# EVK-NORA-W1_SCHEM_0002_Power.net
KiCad netlist of a schematic drawn in Altium Designer
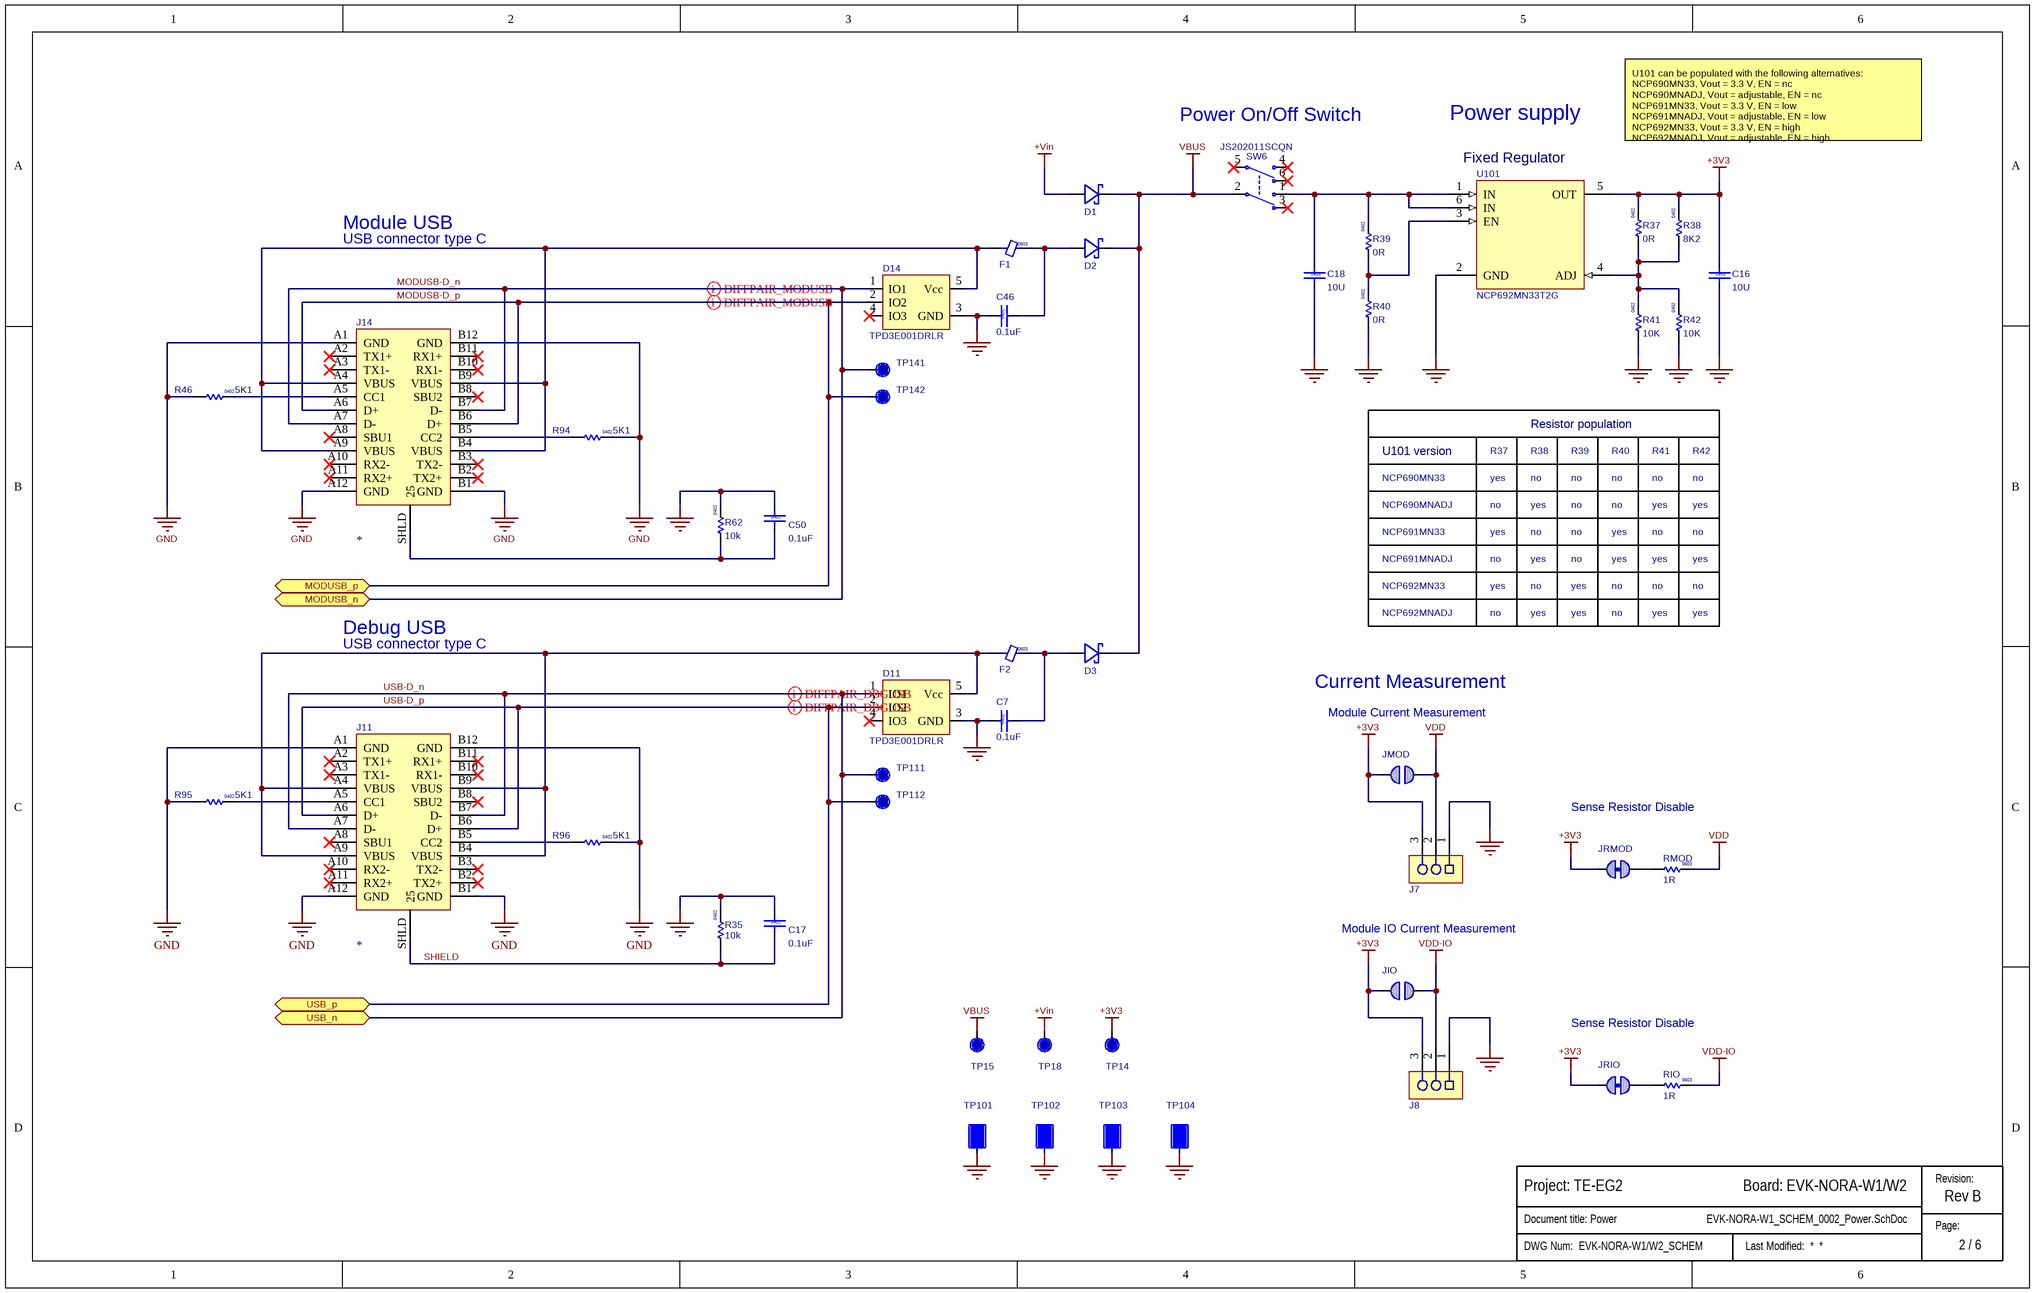
[diagram p0: EVK-NORA-W1_SCHEM_0002_Power.SchDoc]

(export (version "E")
  (design (tool "Eeschema 10.0.6"))
  (components
    (comp (ref "C7")
      (value "0.1uF")
      (footprint "Cap 0402 HD")
      (description "Cap, Ceramic 0.1uF 10V 10% X5R 0402")
      (fields
        (field (name "SIZE") "0402")
        (field (name "PART NUMBER") "120-00016")
        (field (name "MANUFACTURER") "Murata Electronics North America")
      )
      (libsource (lib "Arena_Parts_DB_Lib") (part "Cap Chip"))
    )
    (comp (ref "C16")
      (value "10U")
      (footprint "Cap 0603 HD")
      (description "CAP CER X7R 0603 10U 20% 10V")
      (fields
        (field (name "SIZE") "0603")
        (field (name "PART NUMBER") "UBXH01-0000310")
        (field (name "TOLERANCE") "20%")
        (field (name "EDITOR") "michael.hein")
        (field (name "RELEASED BY") "martin.grasse")
      )
      (libsource (lib "UBX_Parts_DB_Lib") (part "Cap Chip"))
    )
    (comp (ref "C17")
      (value "0.1uF")
      (footprint "Cap 0402 HD")
      (description "Cap, Ceramic 0.1uF 10V 10% X5R 0402")
      (fields
        (field (name "SIZE") "0402")
        (field (name "PART NUMBER") "120-00016")
        (field (name "MANUFACTURER") "Murata Electronics North America")
      )
      (libsource (lib "Arena_Parts_DB_Lib") (part "Cap Chip"))
    )
    (comp (ref "C18")
      (value "10U")
      (footprint "Cap 0603 HD")
      (description "CAP CER X7R 0603 10U 20% 10V")
      (fields
        (field (name "SIZE") "0603")
        (field (name "PART NUMBER") "UBXH01-0000310")
        (field (name "TOLERANCE") "20%")
        (field (name "EDITOR") "michael.hein")
        (field (name "RELEASED BY") "martin.grasse")
      )
      (libsource (lib "UBX_Parts_DB_Lib") (part "Cap Chip"))
    )
    (comp (ref "C46")
      (value "0.1uF")
      (footprint "Cap 0402 HD")
      (description "Cap, Ceramic 0.1uF 10V 10% X5R 0402")
      (fields
        (field (name "SIZE") "0402")
        (field (name "PART NUMBER") "120-00016")
        (field (name "MANUFACTURER") "Murata Electronics North America")
      )
      (libsource (lib "Arena_Parts_DB_Lib") (part "Cap Chip"))
    )
    (comp (ref "C50")
      (value "0.1uF")
      (footprint "Cap 0402 HD")
      (description "Cap, Ceramic 0.1uF 10V 10% X5R 0402")
      (fields
        (field (name "SIZE") "0402")
        (field (name "PART NUMBER") "120-00016")
        (field (name "MANUFACTURER") "Murata Electronics North America")
      )
      (libsource (lib "Arena_Parts_DB_Lib") (part "Cap Chip"))
    )
    (comp (ref "D1")
      (value "110-00005")
      (footprint "SOD-123F_U")
      (description "Diode, Schottky, 20V 1A SOD-123F, 340mV Vf @ 1A\nMBR120VLSFT3G")
      (fields (field (name "VOLTAGE") "20V"))
      (libsource (lib "Arena_Parts_DB_Lib") (part "Diode_Schottky"))
    )
    (comp (ref "D2")
      (value "110-00005")
      (footprint "SOD-123F_U")
      (description "Diode, Schottky, 20V 1A SOD-123F, 340mV Vf @ 1A\nMBR120VLSFT3G")
      (fields (field (name "VOLTAGE") "20V"))
      (libsource (lib "Arena_Parts_DB_Lib") (part "Diode_Schottky"))
    )
    (comp (ref "D3")
      (value "110-00005")
      (footprint "SOD-123F_U")
      (description "Diode, Schottky, 20V 1A SOD-123F, 340mV Vf @ 1A\nMBR120VLSFT3G")
      (fields (field (name "VOLTAGE") "20V"))
      (libsource (lib "Arena_Parts_DB_Lib") (part "Diode_Schottky"))
    )
    (comp (ref "D11")
      (value "110-00018")
      (footprint "SOT-553")
      (description "LOW-CAPACITANCE 3-CHANNEL ESD-PROTECTION ARRAY")
      (fields
        (field (name "MANUFACTURER P/N") "TPD3E001DRLR")
        (field (name "MANUFACTURER") "Texas Instruments")
        (field (name "VOLTAGE") "5V")
      )
      (libsource (lib "Arena_Parts_DB_Lib") (part "TPD3E001"))
    )
    (comp (ref "D14")
      (value "110-00018")
      (footprint "SOT-553")
      (description "LOW-CAPACITANCE 3-CHANNEL ESD-PROTECTION ARRAY")
      (fields
        (field (name "MANUFACTURER P/N") "TPD3E001DRLR")
        (field (name "MANUFACTURER") "Texas Instruments")
        (field (name "VOLTAGE") "5V")
      )
      (libsource (lib "Arena_Parts_DB_Lib") (part "TPD3E001"))
    )
    (comp (ref "F1")
      (value "UBXH08-0000001")
      (footprint "IND 0603 HD")
      (description "FERRITE BEAD 0603 600 OHM AT 100MHZ 600OHM 500mA")
      (fields
        (field (name "SIZE") "0603")
        (field (name "MANUFACTURER") "TDK Corporation")
        (field (name "EDITOR") "daniel.hurni")
        (field (name "RELEASED BY") "martin.frauchiger")
      )
      (libsource (lib "UBX_Parts_DB_Lib") (part "FB sm"))
    )
    (comp (ref "F2")
      (value "UBXH08-0000001")
      (footprint "IND 0603 HD")
      (description "FERRITE BEAD 0603 600 OHM AT 100MHZ 600OHM 500mA")
      (fields
        (field (name "SIZE") "0603")
        (field (name "MANUFACTURER") "TDK Corporation")
        (field (name "EDITOR") "daniel.hurni")
        (field (name "RELEASED BY") "martin.frauchiger")
      )
      (libsource (lib "UBX_Parts_DB_Lib") (part "FB sm"))
    )
    (comp (ref "J7")
      (value "130-00105")
      (footprint "HDR-0.1P-3Pin-1Row-SMT")
      (description "Header, 0.100\" Pitch, 3 Pin, Vertical SMT")
      (fields (field (name "MANUFACTURER") "Harwin Inc"))
      (libsource (lib "Arena_Parts_DB_Lib") (part "CON-3Pin_1Row"))
    )
    (comp (ref "J8")
      (value "130-00105")
      (footprint "HDR-0.1P-3Pin-1Row-SMT")
      (description "Header, 0.100\" Pitch, 3 Pin, Vertical SMT")
      (fields (field (name "MANUFACTURER") "Harwin Inc"))
      (libsource (lib "Arena_Parts_DB_Lib") (part "CON-3Pin_1Row"))
    )
    (comp (ref "J11")
      (value "130-00150")
      (footprint "CON_USB-C-RA_W-6Tabs")
      (description "Connector, USB-C Receptacle, 24 Position, Surface Mount, Right Angle, Horizontal, 20V")
      (fields (field (name "MANUFACTURER P/N") "*") (field (name "VOLTAGE") "20V"))
      (libsource (lib "Arena_Parts_DB_Lib") (part "USB-24Pin_W-Shield"))
    )
    (comp (ref "J14")
      (value "130-00150")
      (footprint "CON_USB-C-RA_W-6Tabs")
      (description "Connector, USB-C Receptacle, 24 Position, Surface Mount, Right Angle, Horizontal, 20V")
      (fields (field (name "MANUFACTURER P/N") "*") (field (name "VOLTAGE") "20V"))
      (libsource (lib "Arena_Parts_DB_Lib") (part "USB-24Pin_W-Shield"))
    )
    (comp (ref "JIO")
      (value "Solderbridge-OpenDNP")
      (footprint "Solderbridge-Open")
      (description "Solderbridge-Open")
      (fields (field (name "ADDED BY") "Paul B"))
      (libsource (lib "LEGACY_Rigado_AltiumLib") (part "Solderbridge-Open"))
    )
    (comp (ref "JMOD")
      (value "Solderbridge-OpenDNP")
      (footprint "Solderbridge-Open")
      (description "Solderbridge-Open")
      (fields (field (name "ADDED BY") "Paul B"))
      (libsource (lib "LEGACY_Rigado_AltiumLib") (part "Solderbridge-Open"))
    )
    (comp (ref "JRIO")
      (value "Solderbridge-ShortDNP")
      (footprint "Solderbridge-Short")
      (description "Solderbridge-Short")
      (fields (field (name "ADDED BY") "Paul B"))
      (libsource (lib "LEGACY_Rigado_AltiumLib") (part "Solderbridge-Short"))
    )
    (comp (ref "JRMOD")
      (value "Solderbridge-ShortDNP")
      (footprint "Solderbridge-Short")
      (description "Solderbridge-Short")
      (fields (field (name "ADDED BY") "Paul B"))
      (libsource (lib "LEGACY_Rigado_AltiumLib") (part "Solderbridge-Short"))
    )
    (comp (ref "R35")
      (value "10k")
      (footprint "RES 0402 HD")
      (description "Resistor 10k ohm 1% 1/16W, 0402")
      (fields
        (field (name "SIZE") "0402")
        (field (name "PART NUMBER") "180-00024")
        (field (name "MANUFACTURER") "Rohm Semiconductor")
      )
      (libsource (lib "Arena_Parts_DB_Lib") (part "Res sm"))
    )
    (comp (ref "R37")
      (value "0R")
      (footprint "RES 0402 HD")
      (description "RES THICK FILM CHIP 0402 0R 0 100mW")
      (fields
        (field (name "SIZE") "0402")
        (field (name "PART NUMBER") "UBXH18-0003002")
        (field (name "TOLERANCE") "0")
        (field (name "EDITOR") "charlotte.biber")
        (field (name "RELEASED BY") "peter.mueller")
      )
      (libsource (lib "UBX_Parts_DB_Lib") (part "Res sm"))
    )
    (comp (ref "R38")
      (value "8K2")
      (footprint "RES 0402 HD")
      (description "RES THICK FILM CHIP 0402 8K2 1% 63mW")
      (fields
        (field (name "SIZE") "0402")
        (field (name "PART NUMBER") "UBXH18-0000138")
        (field (name "TOLERANCE") "1%")
        (field (name "EDITOR") "matej.budin")
        (field (name "RELEASED BY") "pasquale.scorca")
      )
      (libsource (lib "UBX_Parts_DB_Lib") (part "Res sm"))
    )
    (comp (ref "R39")
      (value "0R")
      (footprint "RES 0402 HD")
      (description "RES THICK FILM CHIP 0402 0R 0 100mW")
      (fields
        (field (name "SIZE") "0402")
        (field (name "PART NUMBER") "UBXH18-0003002")
        (field (name "TOLERANCE") "0")
        (field (name "EDITOR") "charlotte.biber")
        (field (name "RELEASED BY") "peter.mueller")
      )
      (libsource (lib "UBX_Parts_DB_Lib") (part "Res sm"))
    )
    (comp (ref "R40")
      (value "0R")
      (footprint "RES 0402 HD")
      (description "RES THICK FILM CHIP 0402 0R 0 100mW")
      (fields
        (field (name "SIZE") "0402")
        (field (name "PART NUMBER") "UBXH18-0003002")
        (field (name "TOLERANCE") "0")
        (field (name "EDITOR") "charlotte.biber")
        (field (name "RELEASED BY") "peter.mueller")
      )
      (libsource (lib "UBX_Parts_DB_Lib") (part "Res sm"))
    )
    (comp (ref "R41")
      (value "10K")
      (footprint "RES 0402 HD")
      (description "RES THICK FILM CHIP 0402 10K 1% 63mW")
      (fields
        (field (name "SIZE") "0402")
        (field (name "PART NUMBER") "UBXH18-0000065")
        (field (name "TOLERANCE") "1%")
        (field (name "EDITOR") "erian.bezhani")
        (field (name "RELEASED BY") "massimo.vlacci")
      )
      (libsource (lib "UBX_Parts_DB_Lib") (part "Res sm"))
    )
    (comp (ref "R42")
      (value "10K")
      (footprint "RES 0402 HD")
      (description "RES THICK FILM CHIP 0402 10K 1% 63mW")
      (fields
        (field (name "SIZE") "0402")
        (field (name "PART NUMBER") "UBXH18-0000065")
        (field (name "TOLERANCE") "1%")
        (field (name "EDITOR") "erian.bezhani")
        (field (name "RELEASED BY") "massimo.vlacci")
      )
      (libsource (lib "UBX_Parts_DB_Lib") (part "Res sm"))
    )
    (comp (ref "R46")
      (value "5K1")
      (footprint "RES 0402 HD")
      (description "RES THICK FILM CHIP 0402 5K1 5% 100mW")
      (fields
        (field (name "SIZE") "0402")
        (field (name "PART NUMBER") "UBXH18-0008066")
        (field (name "TOLERANCE") "5%")
        (field (name "EDITOR") "alvaro.nussbaum")
        (field (name "RELEASED BY") "roland.rust")
      )
      (libsource (lib "UBX_Parts_DB_Lib") (part "Res sm"))
    )
    (comp (ref "R62")
      (value "10k")
      (footprint "RES 0402 HD")
      (description "Resistor 10k ohm 1% 1/16W, 0402")
      (fields
        (field (name "SIZE") "0402")
        (field (name "PART NUMBER") "180-00024")
        (field (name "MANUFACTURER") "Rohm Semiconductor")
      )
      (libsource (lib "Arena_Lib") (part "Res sm"))
    )
    (comp (ref "R94")
      (value "5K1")
      (footprint "RES 0402 HD")
      (description "RES THICK FILM CHIP 0402 5K1 5% 100mW")
      (fields
        (field (name "SIZE") "0402")
        (field (name "PART NUMBER") "UBXH18-0008066")
        (field (name "TOLERANCE") "5%")
        (field (name "EDITOR") "alvaro.nussbaum")
        (field (name "RELEASED BY") "roland.rust")
      )
      (libsource (lib "UBX_Parts_DB_Lib") (part "Res sm"))
    )
    (comp (ref "R95")
      (value "5K1")
      (footprint "RES 0402 HD")
      (description "RES THICK FILM CHIP 0402 5K1 5% 100mW")
      (fields
        (field (name "SIZE") "0402")
        (field (name "PART NUMBER") "UBXH18-0008066")
        (field (name "TOLERANCE") "5%")
        (field (name "EDITOR") "alvaro.nussbaum")
        (field (name "RELEASED BY") "roland.rust")
      )
      (libsource (lib "UBX_Parts_DB_Lib") (part "Res sm"))
    )
    (comp (ref "R96")
      (value "5K1")
      (footprint "RES 0402 HD")
      (description "RES THICK FILM CHIP 0402 5K1 5% 100mW")
      (fields
        (field (name "SIZE") "0402")
        (field (name "PART NUMBER") "UBXH18-0008066")
        (field (name "TOLERANCE") "5%")
        (field (name "EDITOR") "alvaro.nussbaum")
        (field (name "RELEASED BY") "roland.rust")
      )
      (libsource (lib "UBX_Parts_DB_Lib") (part "Res sm"))
    )
    (comp (ref "RIO")
      (value "1R")
      (footprint "RES 0603 HD")
      (description "Resistor 1 ohm 1%, 1/10W, 0603")
      (fields
        (field (name "SIZE") "0603")
        (field (name "PART NUMBER") "180-00109")
        (field (name "MANUFACTURER") "Samsung Electro-Mechanics America, Inc")
      )
      (libsource (lib "Arena_Parts_DB_Lib") (part "Res sm"))
    )
    (comp (ref "RMOD")
      (value "1R")
      (footprint "RES 0603 HD")
      (description "Resistor 1 ohm 1%, 1/10W, 0603")
      (fields
        (field (name "SIZE") "0603")
        (field (name "PART NUMBER") "180-00109")
        (field (name "MANUFACTURER") "Samsung Electro-Mechanics America, Inc")
      )
      (libsource (lib "Arena_Parts_DB_Lib") (part "Res sm"))
    )
    (comp (ref "SW6")
      (value "137-00006")
      (footprint "SW_Slide_DPDT_JS202011SCQN")
      (description "SWITCH SLIDE DPDT 300MA 6V SMD")
      (fields
        (field (name "MANUFACTURER P/N") "JS202011SCQN")
        (field (name "MANUFACTURER") "C&K Components")
        (field (name "VOLTAGE") "6V")
      )
      (libsource (lib "Arena_Parts_DB_Lib") (part "SW_DPDT"))
    )
    (comp (ref "TP14")
      (value "TP")
      (footprint "TP10R")
      (description "Testpoint, Round 1.0mm Dia")
      (fields
        (field (name "PART NUMBER") "TP10R")
        (field (name "ADDED BY") "Jeremy D")
        (field (name "CHECKED BY") "Paul B")
      )
      (libsource (lib "LEGACY_Rigado_AltiumLib") (part "TP_R"))
    )
    (comp (ref "TP15")
      (value "TP")
      (footprint "TP10R")
      (description "Testpoint, Round 1.0mm Dia")
      (fields
        (field (name "PART NUMBER") "TP10R")
        (field (name "ADDED BY") "Jeremy D")
        (field (name "CHECKED BY") "Paul B")
      )
      (libsource (lib "LEGACY_Rigado_AltiumLib") (part "TP_R"))
    )
    (comp (ref "TP18")
      (value "TP")
      (footprint "TP10R")
      (description "Testpoint, Round 1.0mm Dia")
      (fields
        (field (name "PART NUMBER") "TP10R")
        (field (name "ADDED BY") "Jeremy D")
        (field (name "CHECKED BY") "Paul B")
      )
      (libsource (lib "LEGACY_Rigado_AltiumLib") (part "TP_R"))
    )
    (comp (ref "TP101")
      (value "TP4.5x3SqDNP")
      (footprint "TP4.5x3Sq")
      (description "Testpoint, Rectangular 4.5mm x 3mm")
      (fields (field (name "PART NUMBER") "TP4.5x3Sq") (field (name "ADDED BY") "Jeremy D"))
      (libsource (lib "LEGACY_Rigado_AltiumLib") (part "TP_Sq"))
    )
    (comp (ref "TP102")
      (value "TP4.5x3SqDNP")
      (footprint "TP4.5x3Sq")
      (description "Testpoint, Rectangular 4.5mm x 3mm")
      (fields (field (name "PART NUMBER") "TP4.5x3Sq") (field (name "ADDED BY") "Jeremy D"))
      (libsource (lib "LEGACY_Rigado_AltiumLib") (part "TP_Sq"))
    )
    (comp (ref "TP103")
      (value "TP4.5x3SqDNP")
      (footprint "TP4.5x3Sq")
      (description "Testpoint, Rectangular 4.5mm x 3mm")
      (fields (field (name "PART NUMBER") "TP4.5x3Sq") (field (name "ADDED BY") "Jeremy D"))
      (libsource (lib "LEGACY_Rigado_AltiumLib") (part "TP_Sq"))
    )
    (comp (ref "TP104")
      (value "TP4.5x3SqDNP")
      (footprint "TP4.5x3Sq")
      (description "Testpoint, Rectangular 4.5mm x 3mm")
      (fields (field (name "PART NUMBER") "TP4.5x3Sq") (field (name "ADDED BY") "Jeremy D"))
      (libsource (lib "LEGACY_Rigado_AltiumLib") (part "TP_Sq"))
    )
    (comp (ref "TP111")
      (value "TP")
      (footprint "TP10R")
      (description "Testpoint, Round 1.0mm Dia")
      (fields
        (field (name "PART NUMBER") "TP10R")
        (field (name "ADDED BY") "Jeremy D")
        (field (name "CHECKED BY") "Paul B")
      )
      (libsource (lib "LEGACY_Rigado_AltiumLib") (part "TP_R"))
    )
    (comp (ref "TP112")
      (value "TP")
      (footprint "TP10R")
      (description "Testpoint, Round 1.0mm Dia")
      (fields
        (field (name "PART NUMBER") "TP10R")
        (field (name "ADDED BY") "Jeremy D")
        (field (name "CHECKED BY") "Paul B")
      )
      (libsource (lib "LEGACY_Rigado_AltiumLib") (part "TP_R"))
    )
    (comp (ref "TP141")
      (value "TP")
      (footprint "TP10R")
      (description "Testpoint, Round 1.0mm Dia")
      (fields
        (field (name "PART NUMBER") "TP10R")
        (field (name "ADDED BY") "Jeremy D")
        (field (name "CHECKED BY") "Paul B")
      )
      (libsource (lib "LEGACY_Rigado_AltiumLib") (part "TP_R"))
    )
    (comp (ref "TP142")
      (value "TP")
      (footprint "TP10R")
      (description "Testpoint, Round 1.0mm Dia")
      (fields
        (field (name "PART NUMBER") "TP10R")
        (field (name "ADDED BY") "Jeremy D")
        (field (name "CHECKED BY") "Paul B")
      )
      (libsource (lib "LEGACY_Rigado_AltiumLib") (part "TP_R"))
    )
    (comp (ref "U101")
      (value "NCP692MN33T2G")
      (footprint "DFN-PSON.1P3X3-7pin_HS-7N")
      (description "LOW DROPOUT REGULATOR ON SEMICONDUCTOR NCP692MN33T2G 6DFN 3.3V 6V 1A")
      (fields
        (field (name "PART NUMBER") "UBXH12-0000459")
        (field (name "MANUFACTURER") "ON Semiconductor")
        (field (name "EDITOR") "hakan.ekfors")
        (field (name "RELEASED BY") "markus.wejrot")
      )
      (libsource (lib "UBX_Parts_DB_Lib") (part "NCP692MN33T2G"))
    )
  )
  (nets
    (net (code "1") (name "+3V3") (class "Default")
      (node (ref "C16") (pin "1") (pinfunction "1_1") (pintype "passive"))
      (node (ref "J7") (pin "3") (pinfunction "3_3") (pintype "passive"))
      (node (ref "J8") (pin "3") (pinfunction "3_3") (pintype "passive"))
      (node (ref "JIO") (pin "2") (pinfunction "2_2") (pintype "passive"))
      (node (ref "JMOD") (pin "2") (pinfunction "2_2") (pintype "passive"))
      (node (ref "JRIO") (pin "2") (pinfunction "2_2") (pintype "passive"))
      (node (ref "JRMOD") (pin "2") (pinfunction "2_2") (pintype "passive"))
      (node (ref "R37") (pin "2") (pinfunction "2_2") (pintype "passive"))
      (node (ref "R38") (pin "2") (pinfunction "2_2") (pintype "passive"))
      (node (ref "TP14") (pin "1") (pintype "passive"))
      (node (ref "U101") (pin "5") (pinfunction "OUT_5") (pintype "power_in"))
    )
    (net (code "2") (name "+Vin") (class "Default")
      (node (ref "D1") (pin "A") (pinfunction "Anode_A") (pintype "passive"))
      (node (ref "TP18") (pin "1") (pintype "passive"))
    )
    (net (code "3") (name "/MODUSB-D_n") (class "Default")
      (node (ref "D14") (pin "1") (pinfunction "IO1_1") (pintype "passive"))
      (node (ref "J14") (pin "A7") (pinfunction "D-_A7") (pintype "passive"))
      (node (ref "J14") (pin "B7") (pinfunction "D-_B7") (pintype "passive"))
      (node (ref "TP141") (pin "1") (pintype "passive"))
    )
    (net (code "4") (name "/MODUSB-D_p") (class "Default")
      (node (ref "D14") (pin "2") (pinfunction "IO2_2") (pintype "passive"))
      (node (ref "J14") (pin "A6") (pinfunction "D+_A6") (pintype "passive"))
      (node (ref "J14") (pin "B6") (pinfunction "D+_B6") (pintype "passive"))
      (node (ref "TP142") (pin "1") (pintype "passive"))
    )
    (net (code "5") (name "/SHIELD") (class "Default")
      (node (ref "C17") (pin "2") (pinfunction "2_2") (pintype "passive"))
      (node (ref "J11") (pin "SHLD") (pinfunction "25_SHLD") (pintype "passive"))
      (node (ref "R35") (pin "1") (pinfunction "1_1") (pintype "passive"))
    )
    (net (code "6") (name "/USB-D_n") (class "Default")
      (node (ref "D11") (pin "1") (pinfunction "IO1_1") (pintype "passive"))
      (node (ref "J11") (pin "A7") (pinfunction "D-_A7") (pintype "passive"))
      (node (ref "J11") (pin "B7") (pinfunction "D-_B7") (pintype "passive"))
      (node (ref "TP111") (pin "1") (pintype "passive"))
    )
    (net (code "7") (name "/USB-D_p") (class "Default")
      (node (ref "D11") (pin "2") (pinfunction "IO2_2") (pintype "passive"))
      (node (ref "J11") (pin "A6") (pinfunction "D+_A6") (pintype "passive"))
      (node (ref "J11") (pin "B6") (pinfunction "D+_B6") (pintype "passive"))
      (node (ref "TP112") (pin "1") (pintype "passive"))
    )
    (net (code "8") (name "GND") (class "Default")
      (node (ref "C16") (pin "2") (pinfunction "2_2") (pintype "passive"))
      (node (ref "C17") (pin "1") (pinfunction "1_1") (pintype "passive"))
      (node (ref "C18") (pin "2") (pinfunction "2_2") (pintype "passive"))
      (node (ref "C46") (pin "1") (pinfunction "1_1") (pintype "passive"))
      (node (ref "C50") (pin "1") (pinfunction "1_1") (pintype "passive"))
      (node (ref "C7") (pin "1") (pinfunction "1_1") (pintype "passive"))
      (node (ref "D11") (pin "3") (pinfunction "GND_3") (pintype "power_in"))
      (node (ref "D14") (pin "3") (pinfunction "GND_3") (pintype "power_in"))
      (node (ref "J11") (pin "A1") (pinfunction "GND_A1") (pintype "passive"))
      (node (ref "J11") (pin "A12") (pinfunction "GND_A12") (pintype "passive"))
      (node (ref "J11") (pin "B1") (pinfunction "GND_B1") (pintype "passive"))
      (node (ref "J11") (pin "B12") (pinfunction "GND_B12") (pintype "passive"))
      (node (ref "J14") (pin "A1") (pinfunction "GND_A1") (pintype "passive"))
      (node (ref "J14") (pin "A12") (pinfunction "GND_A12") (pintype "passive"))
      (node (ref "J14") (pin "B1") (pinfunction "GND_B1") (pintype "passive"))
      (node (ref "J14") (pin "B12") (pinfunction "GND_B12") (pintype "passive"))
      (node (ref "J7") (pin "1") (pinfunction "1_1") (pintype "passive"))
      (node (ref "J8") (pin "1") (pinfunction "1_1") (pintype "passive"))
      (node (ref "R35") (pin "2") (pinfunction "2_2") (pintype "passive"))
      (node (ref "R40") (pin "1") (pinfunction "1_1") (pintype "passive"))
      (node (ref "R41") (pin "1") (pinfunction "1_1") (pintype "passive"))
      (node (ref "R42") (pin "1") (pinfunction "1_1") (pintype "passive"))
      (node (ref "R46") (pin "1") (pinfunction "1_1") (pintype "passive"))
      (node (ref "R62") (pin "2") (pinfunction "2_2") (pintype "passive"))
      (node (ref "R94") (pin "2") (pinfunction "2_2") (pintype "passive"))
      (node (ref "R95") (pin "1") (pinfunction "1_1") (pintype "passive"))
      (node (ref "R96") (pin "2") (pinfunction "2_2") (pintype "passive"))
      (node (ref "TP101") (pin "1") (pintype "passive"))
      (node (ref "TP102") (pin "1") (pintype "passive"))
      (node (ref "TP103") (pin "1") (pintype "passive"))
      (node (ref "TP104") (pin "1") (pintype "passive"))
      (node (ref "U101") (pin "2") (pinfunction "GND_2") (pintype "power_in"))
    )
    (net (code "9") (name "Net-(D2-Anode)") (class "Default")
      (node (ref "C46") (pin "2") (pinfunction "2_2") (pintype "passive"))
      (node (ref "D2") (pin "A") (pinfunction "Anode_A") (pintype "passive"))
      (node (ref "F1") (pin "2") (pinfunction "2_2") (pintype "passive"))
    )
    (net (code "10") (name "Net-(D3-Anode)") (class "Default")
      (node (ref "C7") (pin "2") (pinfunction "2_2") (pintype "passive"))
      (node (ref "D3") (pin "A") (pinfunction "Anode_A") (pintype "passive"))
      (node (ref "F2") (pin "2") (pinfunction "2_2") (pintype "passive"))
    )
    (net (code "11") (name "Net-(D11-Vcc)") (class "Default")
      (node (ref "D11") (pin "5") (pinfunction "Vcc_5") (pintype "power_in"))
      (node (ref "F2") (pin "1") (pinfunction "1_1") (pintype "passive"))
      (node (ref "J11") (pin "A4") (pinfunction "VBUS_A4") (pintype "passive"))
      (node (ref "J11") (pin "A9") (pinfunction "VBUS_A9") (pintype "passive"))
      (node (ref "J11") (pin "B4") (pinfunction "VBUS_B4") (pintype "passive"))
      (node (ref "J11") (pin "B9") (pinfunction "VBUS_B9") (pintype "passive"))
    )
    (net (code "12") (name "Net-(D14-Vcc)") (class "Default")
      (node (ref "D14") (pin "5") (pinfunction "Vcc_5") (pintype "power_in"))
      (node (ref "F1") (pin "1") (pinfunction "1_1") (pintype "passive"))
      (node (ref "J14") (pin "A4") (pinfunction "VBUS_A4") (pintype "passive"))
      (node (ref "J14") (pin "A9") (pinfunction "VBUS_A9") (pintype "passive"))
      (node (ref "J14") (pin "B4") (pinfunction "VBUS_B4") (pintype "passive"))
      (node (ref "J14") (pin "B9") (pinfunction "VBUS_B9") (pintype "passive"))
    )
    (net (code "13") (name "Net-(J11-CC1)") (class "Default")
      (node (ref "J11") (pin "A5") (pinfunction "CC1_A5") (pintype "passive"))
      (node (ref "R95") (pin "2") (pinfunction "2_2") (pintype "passive"))
    )
    (net (code "14") (name "Net-(J11-CC2)") (class "Default")
      (node (ref "J11") (pin "B5") (pinfunction "CC2_B5") (pintype "passive"))
      (node (ref "R96") (pin "1") (pinfunction "1_1") (pintype "passive"))
    )
    (net (code "15") (name "Net-(J14-25)") (class "Default")
      (node (ref "C50") (pin "2") (pinfunction "2_2") (pintype "passive"))
      (node (ref "J14") (pin "SHLD") (pinfunction "25_SHLD") (pintype "passive"))
      (node (ref "R62") (pin "1") (pinfunction "1_1") (pintype "passive"))
    )
    (net (code "16") (name "Net-(J14-CC1)") (class "Default")
      (node (ref "J14") (pin "A5") (pinfunction "CC1_A5") (pintype "passive"))
      (node (ref "R46") (pin "2") (pinfunction "2_2") (pintype "passive"))
    )
    (net (code "17") (name "Net-(J14-CC2)") (class "Default")
      (node (ref "J14") (pin "B5") (pinfunction "CC2_B5") (pintype "passive"))
      (node (ref "R94") (pin "1") (pinfunction "1_1") (pintype "passive"))
    )
    (net (code "18") (name "Net-(JRIO-Pad1)") (class "Default")
      (node (ref "JRIO") (pin "1") (pinfunction "1_1") (pintype "passive"))
      (node (ref "RIO") (pin "1") (pinfunction "1_1") (pintype "passive"))
    )
    (net (code "19") (name "Net-(JRMOD-Pad1)") (class "Default")
      (node (ref "JRMOD") (pin "1") (pinfunction "1_1") (pintype "passive"))
      (node (ref "RMOD") (pin "1") (pinfunction "1_1") (pintype "passive"))
    )
    (net (code "20") (name "Net-(SW6-N.O-1)") (class "Default")
      (node (ref "C18") (pin "1") (pinfunction "1_1") (pintype "passive"))
      (node (ref "R39") (pin "2") (pinfunction "2_2") (pintype "passive"))
      (node (ref "SW6") (pin "1") (pinfunction "N.O-1_1") (pintype "passive"))
      (node (ref "U101") (pin "1") (pinfunction "IN_1") (pintype "input"))
      (node (ref "U101") (pin "6") (pinfunction "IN_6") (pintype "input"))
    )
    (net (code "21") (name "Net-(U101-ADJ)") (class "Default")
      (node (ref "R37") (pin "1") (pinfunction "1_1") (pintype "passive"))
      (node (ref "R38") (pin "1") (pinfunction "1_1") (pintype "passive"))
      (node (ref "R41") (pin "2") (pinfunction "2_2") (pintype "passive"))
      (node (ref "R42") (pin "2") (pinfunction "2_2") (pintype "passive"))
      (node (ref "U101") (pin "4") (pinfunction "ADJ_4") (pintype "input"))
    )
    (net (code "22") (name "Net-(U101-EN)") (class "Default")
      (node (ref "R39") (pin "1") (pinfunction "1_1") (pintype "passive"))
      (node (ref "R40") (pin "2") (pinfunction "2_2") (pintype "passive"))
      (node (ref "U101") (pin "3") (pinfunction "EN_3") (pintype "input"))
    )
    (net (code "23") (name "VBUS") (class "Default")
      (node (ref "D1") (pin "C") (pinfunction "Cathode_C") (pintype "passive"))
      (node (ref "D2") (pin "C") (pinfunction "Cathode_C") (pintype "passive"))
      (node (ref "D3") (pin "C") (pinfunction "Cathode_C") (pintype "passive"))
      (node (ref "SW6") (pin "2") (pinfunction "COM-1_2") (pintype "passive"))
      (node (ref "TP15") (pin "1") (pintype "passive"))
    )
    (net (code "24") (name "VDD") (class "Default")
      (node (ref "J7") (pin "2") (pinfunction "2_2") (pintype "passive"))
      (node (ref "JMOD") (pin "1") (pinfunction "1_1") (pintype "passive"))
      (node (ref "RMOD") (pin "2") (pinfunction "2_2") (pintype "passive"))
    )
    (net (code "25") (name "VDD-IO") (class "Default")
      (node (ref "J8") (pin "2") (pinfunction "2_2") (pintype "passive"))
      (node (ref "JIO") (pin "1") (pinfunction "1_1") (pintype "passive"))
      (node (ref "RIO") (pin "2") (pinfunction "2_2") (pintype "passive"))
    )
    (net (code "26") (name "unconnected-(D11-IO3-Pad4)") (class "Default")
      (node (ref "D11") (pin "4") (pinfunction "IO3_4") (pintype "passive+no_connect"))
    )
    (net (code "27") (name "unconnected-(D14-IO3-Pad4)") (class "Default")
      (node (ref "D14") (pin "4") (pinfunction "IO3_4") (pintype "passive+no_connect"))
    )
    (net (code "28") (name "unconnected-(J11-RX1+-PadB11)") (class "Default")
      (node (ref "J11") (pin "B11") (pinfunction "RX1+_B11") (pintype "passive+no_connect"))
    )
    (net (code "29") (name "unconnected-(J11-RX1--PadB10)") (class "Default")
      (node (ref "J11") (pin "B10") (pinfunction "RX1-_B10") (pintype "passive+no_connect"))
    )
    (net (code "30") (name "unconnected-(J11-RX2+-PadA11)") (class "Default")
      (node (ref "J11") (pin "A11") (pinfunction "RX2+_A11") (pintype "passive+no_connect"))
    )
    (net (code "31") (name "unconnected-(J11-RX2--PadA10)") (class "Default")
      (node (ref "J11") (pin "A10") (pinfunction "RX2-_A10") (pintype "passive+no_connect"))
    )
    (net (code "32") (name "unconnected-(J11-SBU1-PadA8)") (class "Default")
      (node (ref "J11") (pin "A8") (pinfunction "SBU1_A8") (pintype "passive+no_connect"))
    )
    (net (code "33") (name "unconnected-(J11-SBU2-PadB8)") (class "Default")
      (node (ref "J11") (pin "B8") (pinfunction "SBU2_B8") (pintype "passive+no_connect"))
    )
    (net (code "34") (name "unconnected-(J11-TX1+-PadA2)") (class "Default")
      (node (ref "J11") (pin "A2") (pinfunction "TX1+_A2") (pintype "passive+no_connect"))
    )
    (net (code "35") (name "unconnected-(J11-TX1--PadA3)") (class "Default")
      (node (ref "J11") (pin "A3") (pinfunction "TX1-_A3") (pintype "passive+no_connect"))
    )
    (net (code "36") (name "unconnected-(J11-TX2+-PadB2)") (class "Default")
      (node (ref "J11") (pin "B2") (pinfunction "TX2+_B2") (pintype "passive+no_connect"))
    )
    (net (code "37") (name "unconnected-(J11-TX2--PadB3)") (class "Default")
      (node (ref "J11") (pin "B3") (pinfunction "TX2-_B3") (pintype "passive+no_connect"))
    )
    (net (code "38") (name "unconnected-(J14-RX1+-PadB11)") (class "Default")
      (node (ref "J14") (pin "B11") (pinfunction "RX1+_B11") (pintype "passive+no_connect"))
    )
    (net (code "39") (name "unconnected-(J14-RX1--PadB10)") (class "Default")
      (node (ref "J14") (pin "B10") (pinfunction "RX1-_B10") (pintype "passive+no_connect"))
    )
    (net (code "40") (name "unconnected-(J14-RX2+-PadA11)") (class "Default")
      (node (ref "J14") (pin "A11") (pinfunction "RX2+_A11") (pintype "passive+no_connect"))
    )
    (net (code "41") (name "unconnected-(J14-RX2--PadA10)") (class "Default")
      (node (ref "J14") (pin "A10") (pinfunction "RX2-_A10") (pintype "passive+no_connect"))
    )
    (net (code "42") (name "unconnected-(J14-SBU1-PadA8)") (class "Default")
      (node (ref "J14") (pin "A8") (pinfunction "SBU1_A8") (pintype "passive+no_connect"))
    )
    (net (code "43") (name "unconnected-(J14-SBU2-PadB8)") (class "Default")
      (node (ref "J14") (pin "B8") (pinfunction "SBU2_B8") (pintype "passive+no_connect"))
    )
    (net (code "44") (name "unconnected-(J14-TX1+-PadA2)") (class "Default")
      (node (ref "J14") (pin "A2") (pinfunction "TX1+_A2") (pintype "passive+no_connect"))
    )
    (net (code "45") (name "unconnected-(J14-TX1--PadA3)") (class "Default")
      (node (ref "J14") (pin "A3") (pinfunction "TX1-_A3") (pintype "passive+no_connect"))
    )
    (net (code "46") (name "unconnected-(J14-TX2+-PadB2)") (class "Default")
      (node (ref "J14") (pin "B2") (pinfunction "TX2+_B2") (pintype "passive+no_connect"))
    )
    (net (code "47") (name "unconnected-(J14-TX2--PadB3)") (class "Default")
      (node (ref "J14") (pin "B3") (pinfunction "TX2-_B3") (pintype "passive+no_connect"))
    )
    (net (code "48") (name "unconnected-(SW6-COM-2-Pad5)") (class "Default")
      (node (ref "SW6") (pin "5") (pinfunction "COM-2_5") (pintype "passive+no_connect"))
    )
    (net (code "49") (name "unconnected-(SW6-N.C-1-Pad3)") (class "Default")
      (node (ref "SW6") (pin "3") (pinfunction "N.C-1_3") (pintype "passive+no_connect"))
    )
    (net (code "50") (name "unconnected-(SW6-N.C-2-Pad6)") (class "Default")
      (node (ref "SW6") (pin "6") (pinfunction "N.C-2_6") (pintype "passive+no_connect"))
    )
    (net (code "51") (name "unconnected-(SW6-N.O-2-Pad4)") (class "Default")
      (node (ref "SW6") (pin "4") (pinfunction "N.O-2_4") (pintype "passive+no_connect"))
    )
  )
)
